# USB.net
KiCad netlist of a schematic drawn in Altium Designer
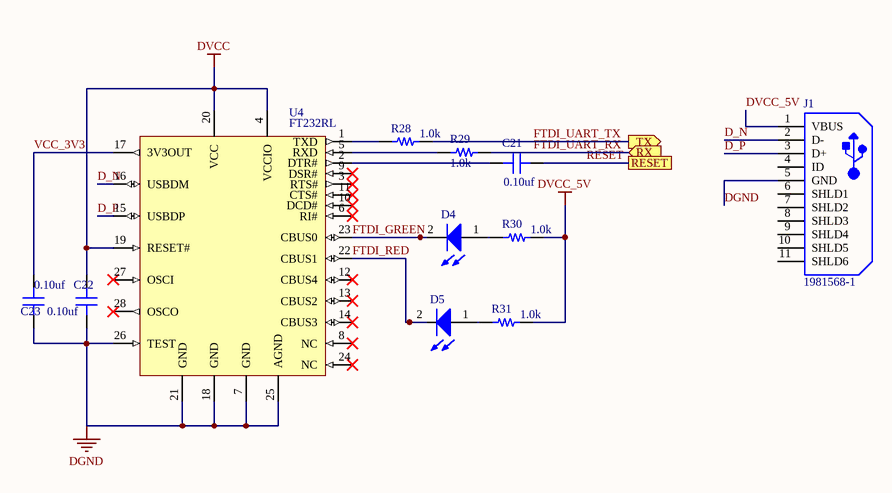
[diagram p0: USB.SchDoc]

(export (version "E")
  (design (tool "Eeschema 10.0.6"))
  (components
    (comp (ref "C21")
      (value "0.10uf")
      (footprint "CAP 0603/1608")
      (fields
        (field (name "Comment") "Capacitor MLCC 0.10uf 25V CAP 0603/1608")
        (field (name "CREATED_BY") "Nick Mah")
      )
      (libsource (lib "Altium-Lib") (part "Capacitor"))
    )
    (comp (ref "C22")
      (value "0.10uf")
      (footprint "CAP 0603/1608")
      (fields
        (field (name "Comment") "Capacitor MLCC 0.10uf 25V CAP 0603/1608")
        (field (name "CREATED_BY") "Nick Mah")
      )
      (libsource (lib "Altium-Lib") (part "Capacitor"))
    )
    (comp (ref "C23")
      (value "0.10uf")
      (footprint "CAP 0603/1608")
      (fields
        (field (name "Comment") "Capacitor MLCC 0.10uf 25V CAP 0603/1608")
        (field (name "CREATED_BY") "Nick Mah")
      )
      (libsource (lib "Altium-Lib") (part "Capacitor"))
    )
    (comp (ref "D4") (value "~") (footprint "0805_LED") (libsource (lib "Altium-Lib") (part "LED")))
    (comp (ref "D5") (value "~") (footprint "0805_LED") (libsource (lib "Altium-Lib") (part "LED")))
    (comp (ref "J1")
      (value "1981568-1")
      (footprint "TECO-1981568-5_V")
      (description "USB Micro Type B")
      (fields (field (name "CREATED_BY") "Aiku"))
      (libsource (lib "Altium-Lib") (part "USB-5-6SHLD"))
    )
    (comp (ref "R28")
      (value "1.0k")
      (footprint "RES 0805/2012")
      (fields
        (field (name "TOLERANCE") "1%")
        (field (name "POWER") "1/4W")
        (field (name "Comment") "Resistor 1.0k 0805 1/4W 1%")
        (field (name "CREATED_BY") "Nick Mah")
      )
      (libsource (lib "Altium-Lib") (part "Resistor"))
    )
    (comp (ref "R29")
      (value "1.0k")
      (footprint "RES 0805/2012")
      (fields
        (field (name "TOLERANCE") "1%")
        (field (name "POWER") "1/4W")
        (field (name "Comment") "Resistor 1.0k 0805 1/4W 1%")
        (field (name "CREATED_BY") "Nick Mah")
      )
      (libsource (lib "Altium-Lib") (part "Resistor"))
    )
    (comp (ref "R30")
      (value "1.0k")
      (footprint "RES 0805/2012")
      (fields
        (field (name "TOLERANCE") "1%")
        (field (name "POWER") "1/4W")
        (field (name "Comment") "Resistor 1.0k 0805 1/4W 1%")
        (field (name "CREATED_BY") "Nick Mah")
      )
      (libsource (lib "Altium-Lib") (part "Resistor"))
    )
    (comp (ref "R31")
      (value "1.0k")
      (footprint "RES 0805/2012")
      (fields
        (field (name "TOLERANCE") "1%")
        (field (name "POWER") "1/4W")
        (field (name "Comment") "Resistor 1.0k 0805 1/4W 1%")
        (field (name "CREATED_BY") "Nick Mah")
      )
      (libsource (lib "Altium-Lib") (part "Resistor"))
    )
    (comp (ref "U4")
      (value "FT232RL")
      (footprint "SSOP-28")
      (fields (field (name "CREATED_BY") "Kyle"))
      (libsource (lib "Altium-Lib") (part "FT232RL"))
    )
  )
  (nets
    (net (code "1") (name "/D_N") (class "Default")
      (node (ref "J1") (pin "2") (pinfunction "D-_2") (pintype "passive"))
      (node (ref "U4") (pin "16") (pinfunction "USBDM_16") (pintype "bidirectional"))
    )
    (net (code "2") (name "/D_P") (class "Default")
      (node (ref "J1") (pin "3") (pinfunction "D+_3") (pintype "passive"))
      (node (ref "U4") (pin "15") (pinfunction "USBDP_15") (pintype "bidirectional"))
    )
    (net (code "3") (name "/FTDI_GREEN") (class "Default")
      (node (ref "D4") (pin "2") (pinfunction "K_2") (pintype "passive"))
      (node (ref "U4") (pin "23") (pinfunction "CBUS0_23") (pintype "bidirectional"))
    )
    (net (code "4") (name "/FTDI_RED") (class "Default")
      (node (ref "D5") (pin "2") (pinfunction "K_2") (pintype "passive"))
      (node (ref "U4") (pin "22") (pinfunction "CBUS1_22") (pintype "bidirectional"))
    )
    (net (code "5") (name "/FTDI_UART_RX") (class "Default")
      (node (ref "R29") (pin "2") (pinfunction "2_2") (pintype "passive"))
    )
    (net (code "6") (name "/FTDI_UART_TX") (class "Default")
      (node (ref "R28") (pin "2") (pinfunction "2_2") (pintype "passive"))
    )
    (net (code "7") (name "/RESET") (class "Default")
      (node (ref "C21") (pin "2") (pinfunction "2_2") (pintype "passive"))
    )
    (net (code "8") (name "/VCC_3V3") (class "Default")
      (node (ref "C23") (pin "2") (pinfunction "2_2") (pintype "passive"))
      (node (ref "U4") (pin "17") (pinfunction "3V3OUT_17") (pintype "output"))
    )
    (net (code "9") (name "DGND") (class "Default")
      (node (ref "C22") (pin "1") (pinfunction "1_1") (pintype "passive"))
      (node (ref "C23") (pin "1") (pinfunction "1_1") (pintype "passive"))
      (node (ref "J1") (pin "5") (pinfunction "GND_5") (pintype "passive"))
      (node (ref "U4") (pin "18") (pinfunction "GND_18") (pintype "passive"))
      (node (ref "U4") (pin "21") (pinfunction "GND_21") (pintype "passive"))
      (node (ref "U4") (pin "25") (pinfunction "AGND_25") (pintype "passive"))
      (node (ref "U4") (pin "26") (pinfunction "TEST_26") (pintype "input"))
      (node (ref "U4") (pin "7") (pinfunction "GND_7") (pintype "passive"))
    )
    (net (code "10") (name "DVCC") (class "Default")
      (node (ref "C22") (pin "2") (pinfunction "2_2") (pintype "passive"))
      (node (ref "U4") (pin "19") (pinfunction "RESET#_19") (pintype "input"))
      (node (ref "U4") (pin "20") (pinfunction "VCC_20") (pintype "passive"))
      (node (ref "U4") (pin "4") (pinfunction "VCCIO_4") (pintype "passive"))
    )
    (net (code "11") (name "DVCC_5V") (class "Default")
      (node (ref "J1") (pin "1") (pinfunction "VBUS_1") (pintype "passive"))
      (node (ref "R30") (pin "2") (pinfunction "2_2") (pintype "passive"))
      (node (ref "R31") (pin "2") (pinfunction "2_2") (pintype "passive"))
    )
    (net (code "12") (name "Net-(D4-A)") (class "Default")
      (node (ref "D4") (pin "1") (pinfunction "A_1") (pintype "passive"))
      (node (ref "R30") (pin "1") (pinfunction "1_1") (pintype "passive"))
    )
    (net (code "13") (name "Net-(D5-A)") (class "Default")
      (node (ref "D5") (pin "1") (pinfunction "A_1") (pintype "passive"))
      (node (ref "R31") (pin "1") (pinfunction "1_1") (pintype "passive"))
    )
    (net (code "14") (name "Net-(U4-DTR#)") (class "Default")
      (node (ref "C21") (pin "1") (pinfunction "1_1") (pintype "passive"))
      (node (ref "U4") (pin "2") (pinfunction "DTR#_2") (pintype "output"))
    )
    (net (code "15") (name "Net-(U4-RXD)") (class "Default")
      (node (ref "R29") (pin "1") (pinfunction "1_1") (pintype "passive"))
      (node (ref "U4") (pin "5") (pinfunction "RXD_5") (pintype "input"))
    )
    (net (code "16") (name "Net-(U4-TXD)") (class "Default")
      (node (ref "R28") (pin "1") (pinfunction "1_1") (pintype "passive"))
      (node (ref "U4") (pin "1") (pinfunction "TXD_1") (pintype "output"))
    )
    (net (code "17") (name "unconnected-(J1-ID-Pad4)") (class "Default")
      (node (ref "J1") (pin "4") (pinfunction "ID_4") (pintype "passive"))
    )
    (net (code "18") (name "unconnected-(J1-SHLD1-Pad6)") (class "Default")
      (node (ref "J1") (pin "6") (pinfunction "SHLD1_6") (pintype "passive"))
    )
    (net (code "19") (name "unconnected-(J1-SHLD2-Pad7)") (class "Default")
      (node (ref "J1") (pin "7") (pinfunction "SHLD2_7") (pintype "passive"))
    )
    (net (code "20") (name "unconnected-(J1-SHLD3-Pad8)") (class "Default")
      (node (ref "J1") (pin "8") (pinfunction "SHLD3_8") (pintype "passive"))
    )
    (net (code "21") (name "unconnected-(J1-SHLD4-Pad9)") (class "Default")
      (node (ref "J1") (pin "9") (pinfunction "SHLD4_9") (pintype "passive"))
    )
    (net (code "22") (name "unconnected-(J1-SHLD5-Pad10)") (class "Default")
      (node (ref "J1") (pin "10") (pinfunction "SHLD5_10") (pintype "passive"))
    )
    (net (code "23") (name "unconnected-(J1-SHLD6-Pad11)") (class "Default")
      (node (ref "J1") (pin "11") (pinfunction "SHLD6_11") (pintype "passive"))
    )
    (net (code "24") (name "unconnected-(U4-CBUS2-Pad13)") (class "Default")
      (node (ref "U4") (pin "13") (pinfunction "CBUS2_13") (pintype "bidirectional+no_connect"))
    )
    (net (code "25") (name "unconnected-(U4-CBUS3-Pad14)") (class "Default")
      (node (ref "U4") (pin "14") (pinfunction "CBUS3_14") (pintype "bidirectional+no_connect"))
    )
    (net (code "26") (name "unconnected-(U4-CBUS4-Pad12)") (class "Default")
      (node (ref "U4") (pin "12") (pinfunction "CBUS4_12") (pintype "bidirectional+no_connect"))
    )
    (net (code "27") (name "unconnected-(U4-CTS#-Pad11)") (class "Default")
      (node (ref "U4") (pin "11") (pinfunction "CTS#_11") (pintype "input+no_connect"))
    )
    (net (code "28") (name "unconnected-(U4-DCD#-Pad10)") (class "Default")
      (node (ref "U4") (pin "10") (pinfunction "DCD#_10") (pintype "input+no_connect"))
    )
    (net (code "29") (name "unconnected-(U4-DSR#-Pad9)") (class "Default")
      (node (ref "U4") (pin "9") (pinfunction "DSR#_9") (pintype "input+no_connect"))
    )
    (net (code "30") (name "unconnected-(U4-NC-Pad8)") (class "Default")
      (node (ref "U4") (pin "8") (pinfunction "NC_8") (pintype "input+no_connect"))
    )
    (net (code "31") (name "unconnected-(U4-NC-Pad24)") (class "Default")
      (node (ref "U4") (pin "24") (pinfunction "NC_24") (pintype "input+no_connect"))
    )
    (net (code "32") (name "unconnected-(U4-OSCI-Pad27)") (class "Default")
      (node (ref "U4") (pin "27") (pinfunction "OSCI_27") (pintype "input+no_connect"))
    )
    (net (code "33") (name "unconnected-(U4-OSCO-Pad28)") (class "Default")
      (node (ref "U4") (pin "28") (pinfunction "OSCO_28") (pintype "output+no_connect"))
    )
    (net (code "34") (name "unconnected-(U4-RI#-Pad6)") (class "Default")
      (node (ref "U4") (pin "6") (pinfunction "RI#_6") (pintype "input+no_connect"))
    )
    (net (code "35") (name "unconnected-(U4-RTS#-Pad3)") (class "Default")
      (node (ref "U4") (pin "3") (pinfunction "RTS#_3") (pintype "output+no_connect"))
    )
  )
)
